# 03_-_CONNECTOR.net
KiCad netlist of a schematic drawn in Altium Designer
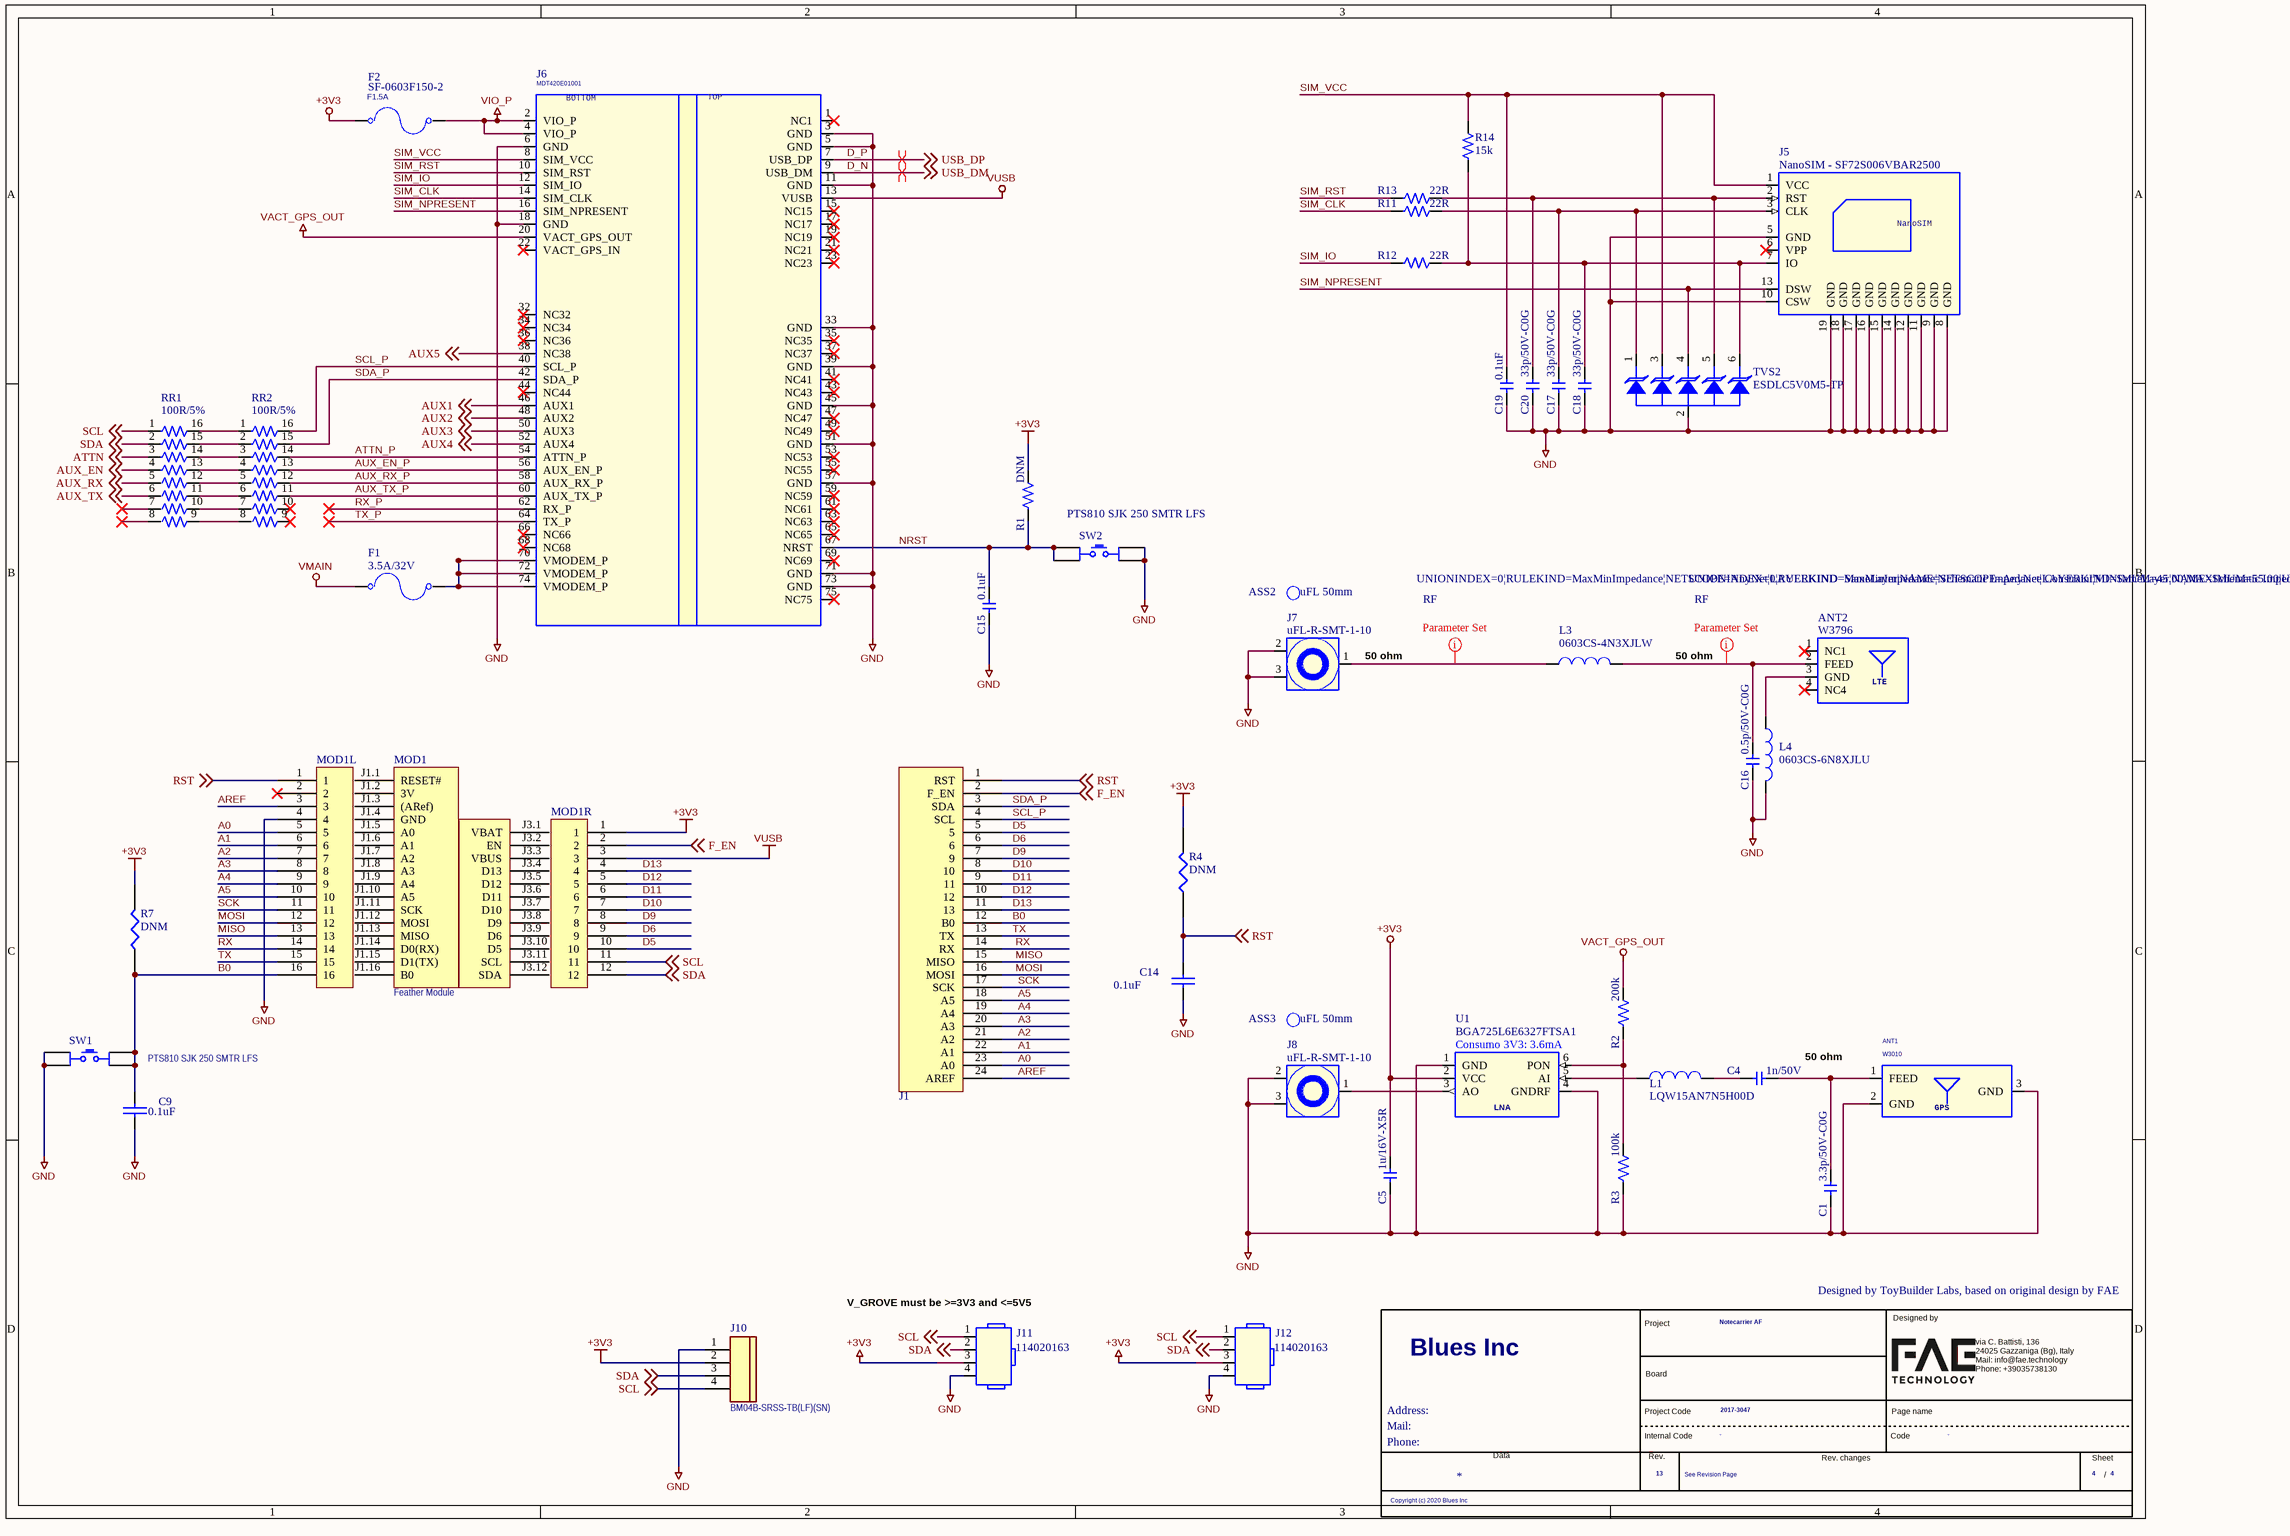
[diagram p0: 03 - CONNECTOR.SchDoc]

(export (version "E")
  (design (tool "Eeschema 10.0.6"))
  (components
    (comp (ref "*")
      (value "MyBlues")
      (fields
        (field (name "ADDRESS") "Address:")
        (field (name "COPYRIGHT") "Copyright (c) 2020 Blues Inc")
        (field (name "CUSTOMER CODE") "-")
        (field (name "CUSTOMERNAME") "Blues Inc")
        (field (name "DATABASE") "-")
        (field (name "DOCUMENTOREV") "See Revision Page")
        (field (name "MAIL") "Mail:")
        (field (name "NOME PROGETTO") "Notecarrier AF")
        (field (name "PAGE COUNT") "4")
        (field (name "PAGE NUMBER") "4")
        (field (name "PHONE") "Phone:")
        (field (name "PROJECT CODE") "2017-3047")
        (field (name "REVISION") "13")
      )
      (libsource (lib "*") (part "MyBlues"))
    )
    (comp (ref "ANT1")
      (value "W3010")
      (footprint "ANT-W3010")
      (description "ANTENNA CHIP 1.575GHZ D=3.2X10X2 W3010 PULSE SMT")
      (libsource (lib "*") (part "ANT - W3010 - GPS-GLONASS"))
    )
    (comp (ref "ANT2")
      (value "W3796")
      (footprint "ANT-W3796")
      (description "ANTENNA CHIP LTE D=40X7X3 W3796 PULSE SMT")
      (libsource (lib "*") (part "ANT - W3796 - LTE"))
    )
    (comp (ref "ASS2")
      (value "uFL 50mm")
      (description "CAVO COAX uFl-uFl 415-0086-050 HIROSE CINCH CONNECTIVITY SOLUTIONS JOHNSON")
      (libsource (lib "*") (part "0000_BASE SIMBOLO_OBJ"))
    )
    (comp (ref "ASS3")
      (value "uFL 50mm")
      (description "CAVO COAX uFl-uFl 415-0086-050 HIROSE CINCH CONNECTIVITY SOLUTIONS JOHNSON")
      (libsource (lib "*") (part "0000_BASE SIMBOLO_OBJ"))
    )
    (comp (ref "C1")
      (value "3.3p/50V-C0G")
      (footprint "CS-C-0402")
      (description "CHIP CAP.CER. 3.3pF 50V 5% C0G 0402")
      (libsource (lib "*") (part "CS-C-0402-3.3p/50V-C0G"))
    )
    (comp (ref "C4")
      (value "1n/50V")
      (footprint "CS-C-0402")
      (description "CHIP CAP.CER. 1nF 50V 10% X7R 0402")
      (libsource (lib "*") (part "CS-C-0402-1n/50V"))
    )
    (comp (ref "C5")
      (value "1u/16V-X5R")
      (footprint "CS-C-0402")
      (description "CHIP CAP.CER. 1uF 16V 10% X5R 0402")
      (libsource (lib "*") (part "CS-C-0402-1u/16-X5R"))
    )
    (comp (ref "C9")
      (value "0.1uF")
      (footprint "CS-C-0402")
      (description "CHIP CAP.CER. 100nF 16V 10% X7R 0402")
      (fields (field (name "MFR") "Yageo"))
      (libsource (lib "Cap_SCH") (part "CAP"))
    )
    (comp (ref "C14")
      (value "0.1uF")
      (footprint "CS-C-0402")
      (description "CHIP CAP.CER. 100nF 16V 10% X7R 0402")
      (fields (field (name "MFR") "Yageo"))
      (libsource (lib "Cap_SCH") (part "CAP"))
    )
    (comp (ref "C15")
      (value "0.1uF")
      (footprint "CS-C-0402")
      (description "CHIP CAP.CER. 100nF 16V 10% X7R 0402")
      (fields (field (name "MFR") "Yageo"))
      (libsource (lib "*") (part "CS-C-0402-100n/16V"))
    )
    (comp (ref "C16")
      (value "0.5p/50V-C0G")
      (footprint "CS-C-0402")
      (description "CHIP CAP.CER. 0.5pF 50V ±0.25 C0G 0402 GRM1555C1HR50CA01D MURATA")
      (libsource (lib "*") (part "CS-C-0402-0.5p/50V-C0G"))
    )
    (comp (ref "C17")
      (value "33p/50V-C0G")
      (footprint "CS-C-0402")
      (description "CHIP CAP.CER. 33pF 50V 5% C0G 0402")
      (libsource (lib "*") (part "CS-C-0402-33p/50V-C0G"))
    )
    (comp (ref "C18")
      (value "33p/50V-C0G")
      (footprint "CS-C-0402")
      (description "CHIP CAP.CER. 33pF 50V 5% C0G 0402")
      (libsource (lib "*") (part "CS-C-0402-33p/50V-C0G"))
    )
    (comp (ref "C19")
      (value "0.1uF")
      (footprint "CS-C-0402")
      (description "CHIP CAP.CER. 100nF 16V 10% X7R 0402")
      (fields (field (name "MFR") "Yageo"))
      (libsource (lib "*") (part "CS-C-0402-100n/16V"))
    )
    (comp (ref "C20")
      (value "33p/50V-C0G")
      (footprint "CS-C-0402")
      (description "CHIP CAP.CER. 33pF 50V 5% C0G 0402")
      (libsource (lib "*") (part "CS-C-0402-33p/50V-C0G"))
    )
    (comp (ref "F1")
      (value "3.5A/32V")
      (footprint "FS-0603")
      (description "FUSIBILE RAPIDO 3.5A 32V 0603 0603SFV350F/32-2 LITTELFUSE SMT")
      (fields (field (name "MPN") "0603SFV350F/32-2"))
      (libsource (lib "*") (part "RAPIDO - 0603SFV350F- 3.5A/32V"))
    )
    (comp (ref "F2")
      (value "SF-0603F150-2")
      (footprint "FS-0603")
      (description "FUSIBILE RAPIDO 1.5A 32V 0603 SF-0603F150-2 BOURNS SMT")
      (libsource (lib "*") (part "RAPIDO - SF-0603F150-2-1.5A/32V"))
    )
    (comp (ref "J1")
      (value "12X1")
      (footprint "WE24S - 2.54")
      (libsource (lib "ATA_BLS_002_NTCR_A0-01_SCHLIB") (part "SIDECON"))
    )
    (comp (ref "J5")
      (value "NanoSIM - SF72S006VBAR2500")
      (footprint "J-NANOSIM-SF72S006VBA")
      (description "CONN. NANOSIM 8P F/90° PUSH-PUSH SF72S006VBAR2500 JAE ELECTRONICS SMT")
      (libsource (lib "*") (part "NANOSIM - J-NANOSIM-SF72S006VBA"))
    )
    (comp (ref "J6")
      (value "MDT420E01001")
      (footprint "J-75-0050-MOS-M2-E")
      (description "CONN. M.2 75P M/90° P=0.5 MDT420E01001 AMPHENOL SMT")
      (libsource (lib "*") (part "AMPHENOL-75 - M-2 KEY E_13"))
    )
    (comp (ref "J7")
      (value "uFL-R-SMT-1-10")
      (footprint "J-3-MDS-UFL")
      (description "CONN. RF M U.FL-R-SMT-1(10) HIROSE SMT")
      (libsource (lib "*") (part "UFL - U-FL-R-SMT-1-10"))
    )
    (comp (ref "J8")
      (value "uFL-R-SMT-1-10")
      (footprint "J-3-MDS-UFL")
      (description "CONN. RF M U.FL-R-SMT-1(10) HIROSE SMT")
      (libsource (lib "*") (part "UFL - U-FL-R-SMT-1-10"))
    )
    (comp (ref "J10")
      (value "BM04B-SRSS-TB(LF)(SN)")
      (footprint "JST_BM04B-SRSS-TB")
      (description "Wire-to-board, 1mm, SMT Vert, 4POS")
      (fields (field (name "MANUFACTURER") "JST"))
      (libsource (lib "TBL Connectors") (part "JST_BM04B-SRSS-TB"))
    )
    (comp (ref "J11")
      (value "114020163")
      (footprint "J-4-0200-MDS-GROVE")
      (description "CONN. GROVE 4P M/D P=2 114020163 SEEDSTUDIO SMT")
      (libsource (lib "*") (part "GROVE - J-4-0200-MDS-GROVE"))
    )
    (comp (ref "J12")
      (value "114020163")
      (footprint "J-4-0200-MDS-GROVE")
      (description "CONN. GROVE 4P M/D P=2 114020163 SEEDSTUDIO SMT")
      (libsource (lib "*") (part "GROVE - J-4-0200-MDS-GROVE"))
    )
    (comp (ref "L1")
      (value "LQW15AN7N5H00D")
      (footprint "LS-0402")
      (description "INDUTTANZA 7.5nH 0.57A 3% A FILO 0402 LQW15AN7N5H00D MURATA SMT")
      (libsource (lib "*") (part "L - LQW15AN7N5H00D - 7.5n/0.57A"))
    )
    (comp (ref "L3")
      (value "0603CS-4N3XJLW")
      (footprint "LS-0603CS")
      (description "INDUTTANZA 4.3nH 0.7A 5% 0603 0603CS-4N3XJLW COILCRAFT SMT")
      (libsource (lib "*") (part "L - 0603CS-4N3XJLW-4.3n/0.7A"))
    )
    (comp (ref "L4")
      (value "0603CS-6N8XJLU")
      (footprint "LS-0603CS")
      (description "INDUTTANZA 6.8nH 0.7A 5% 0603 0603CS-6N8XJLU COILCRAFT SMT")
      (libsource (lib "*") (part "L - 0603CS-6N8XJLU-6.8n/0.7A"))
    )
    (comp (ref "MOD1")
      (value "Feather Module")
      (footprint "FEATHER_COMMON_MOUNTING")
      (description "Socket Footprint for Typical Adafruit Feather Module, SMT socket type")
      (libsource (lib "Notebox Integrated Library") (part "FEATHER_COMMON_MOUNTING"))
    )
    (comp (ref "MOD1L")
      (value "Socket 16-Pin, 0.100 inch (0.335 inch body)")
      (footprint "SOCKET_LFB_16")
      (description "Socket 16-Pin, 0.100 in")
      (libsource (lib "TBLI-Headers") (part "SOCKET_LFB_16"))
    )
    (comp (ref "MOD1R")
      (value "Socket 12-Pin, 0.100 inch (0.335 inch body)")
      (footprint "SOCKET_LFB_12")
      (description "Socket 12-Pin, 0.100 in")
      (libsource (lib "TBLI-Headers") (part "SOCKET_LFB_12"))
    )
    (comp (ref "R1")
      (value "DNM")
      (footprint "RS-0402")
      (description "CHIP RES. 1K 0402 1/16W 1%")
      (libsource (lib "*") (part "RS-0402-1k"))
    )
    (comp (ref "R2")
      (value "200k")
      (footprint "RS-0402")
      (description "CHIP RES. 200K 0402 1/16W 1%")
      (libsource (lib "*") (part "RS-0402-200k"))
    )
    (comp (ref "R3")
      (value "100k")
      (footprint "RS-0402")
      (description "CHIP RES. 100K 0402 1/16W 1%")
      (libsource (lib "*") (part "RS-0402-100k"))
    )
    (comp (ref "R4")
      (value "DNM")
      (footprint "RS-0402")
      (description "SMD Resistors")
      (libsource (lib "Res_SCH") (part "R1_S"))
    )
    (comp (ref "R7")
      (value "DNM")
      (footprint "RS-0402")
      (description "SMD Resistors")
      (libsource (lib "Res_SCH") (part "R1_S"))
    )
    (comp (ref "R11")
      (value "22R")
      (footprint "RS-0603")
      (description "CHIP RES. 22R 0603 1/16W 1%")
      (libsource (lib "*") (part "RS-0603-22r"))
    )
    (comp (ref "R12")
      (value "22R")
      (footprint "RS-0603")
      (description "CHIP RES. 22R 0603 1/16W 1%")
      (libsource (lib "*") (part "RS-0603-22r"))
    )
    (comp (ref "R13")
      (value "22R")
      (footprint "RS-0603")
      (description "CHIP RES. 22R 0603 1/16W 1%")
      (libsource (lib "*") (part "RS-0603-22r"))
    )
    (comp (ref "R14")
      (value "15k")
      (footprint "RS-0402")
      (description "CHIP RES. 15K 0402 1/16W 1%")
      (libsource (lib "*") (part "RS-0402-15k"))
    )
    (comp (ref "RR1")
      (value "100R/5%")
      (footprint "RR-8X-1506")
      (description "RETE RESISTIVA 8R sing. 100R 5% 1506 CONVEX CAY16-101J8LF BOURNS SMT")
      (libsource (lib "*") (part "RR-8X-1506-100r/5%"))
    )
    (comp (ref "RR2")
      (value "100R/5%")
      (footprint "RR-8X-1506")
      (description "RETE RESISTIVA 8R sing. 100R 5% 1506 CONVEX CAY16-101J8LF BOURNS SMT")
      (libsource (lib "*") (part "RR-8X-1506-100r/5%"))
    )
    (comp (ref "SW1")
      (value "PTS810 SJK 250 SMTR LFS")
      (footprint "CK-PTS810-SJx")
      (description "SWITCH TACTILE SPST-NO 0.05A 12V 4.2 mm x 3.2 mm")
      (fields (field (name "MANUFACTURER") "C&K"))
      (libsource (lib "TBL Switches and Buttons") (part "CK_PTS810 SJK 250 SMTR LFS"))
    )
    (comp (ref "SW2")
      (value "PTS810 SJK 250 SMTR LFS")
      (footprint "CK-PTS810-SJx")
      (description "SWITCH TACTILE SPST-NO 0.05A 12V 4.2 mm x 3.2 mm")
      (fields (field (name "MANUFACTURER") "C&K"))
      (libsource (lib "TBL Switches and Buttons") (part "CK_PTS810 SJK 250 SMTR LFS"))
    )
    (comp (ref "TVS2")
      (value "ESDLC5V0M5-TP")
      (footprint "SOT666")
      (description "DIODO TVS TRANSIL UNIDIR. 20W 5V ESDLC5V0M5-TP SOT563 SMT")
      (libsource (lib "*") (part "TVS-UNI5x - ESDLC5V0M5-TP - 5V"))
    )
    (comp (ref "U1")
      (value "BGA725L6E6327FTSA1")
      (footprint "XFDFN6")
      (description "INTEGRATO BGA725L6E6327FTSA1 INFINEON TSLP-6 SMT")
      (fields (field (name "CONSUMO") "Consumo 3V3: 3.6mA"))
      (libsource (lib "*") (part "LNA-RF - BGA725L6E6327FTSA1"))
    )
  )
  (nets
    (net (code "1") (name "+3V3") (class "Default")
      (node (ref "C5") (pin "1") (pinfunction "1_1") (pintype "passive"))
      (node (ref "F2") (pin "1") (pinfunction "1_1") (pintype "passive"))
      (node (ref "J10") (pin "2") (pinfunction "2_2") (pintype "passive"))
      (node (ref "J11") (pin "3") (pinfunction "3_3") (pintype "passive"))
      (node (ref "J12") (pin "3") (pinfunction "3_3") (pintype "passive"))
      (node (ref "MOD1R") (pin "1") (pinfunction "1_1") (pintype "passive"))
      (node (ref "R1") (pin "2") (pinfunction "2_2") (pintype "passive"))
      (node (ref "R4") (pin "2") (pinfunction "2_2") (pintype "passive"))
      (node (ref "R7") (pin "2") (pinfunction "2_2") (pintype "passive"))
      (node (ref "U1") (pin "2") (pinfunction "VCC_2") (pintype "power_in"))
    )
    (net (code "2") (name "/A0") (class "Default")
      (node (ref "J1") (pin "23") (pinfunction "A0_23") (pintype "passive"))
      (node (ref "MOD1L") (pin "5") (pinfunction "5_5") (pintype "passive"))
    )
    (net (code "3") (name "/A1") (class "Default")
      (node (ref "J1") (pin "22") (pinfunction "A1_22") (pintype "passive"))
      (node (ref "MOD1L") (pin "6") (pinfunction "6_6") (pintype "passive"))
    )
    (net (code "4") (name "/A2") (class "Default")
      (node (ref "J1") (pin "21") (pinfunction "A2_21") (pintype "passive"))
      (node (ref "MOD1L") (pin "7") (pinfunction "7_7") (pintype "passive"))
    )
    (net (code "5") (name "/A3") (class "Default")
      (node (ref "J1") (pin "20") (pinfunction "A3_20") (pintype "passive"))
      (node (ref "MOD1L") (pin "8") (pinfunction "8_8") (pintype "passive"))
    )
    (net (code "6") (name "/A4") (class "Default")
      (node (ref "J1") (pin "19") (pinfunction "A4_19") (pintype "passive"))
      (node (ref "MOD1L") (pin "9") (pinfunction "9_9") (pintype "passive"))
    )
    (net (code "7") (name "/A5") (class "Default")
      (node (ref "J1") (pin "18") (pinfunction "A5_18") (pintype "passive"))
      (node (ref "MOD1L") (pin "10") (pinfunction "10_10") (pintype "passive"))
    )
    (net (code "8") (name "/AREF") (class "Default")
      (node (ref "J1") (pin "24") (pinfunction "AREF_24") (pintype "passive"))
      (node (ref "MOD1L") (pin "3") (pinfunction "3_3") (pintype "passive"))
    )
    (net (code "9") (name "/ATTN_P") (class "Default")
      (node (ref "J6") (pin "54") (pinfunction "ATTN_P_54") (pintype "passive"))
      (node (ref "RR2") (pin "14") (pinfunction "14_14") (pintype "passive"))
    )
    (net (code "10") (name "/AUX_EN_P") (class "Default")
      (node (ref "J6") (pin "56") (pinfunction "AUX_EN_P_56") (pintype "passive"))
      (node (ref "RR2") (pin "13") (pinfunction "13_13") (pintype "passive"))
    )
    (net (code "11") (name "/AUX_RX_P") (class "Default")
      (node (ref "J6") (pin "58") (pinfunction "AUX_RX_P_58") (pintype "passive"))
      (node (ref "RR2") (pin "12") (pinfunction "12_12") (pintype "passive"))
    )
    (net (code "12") (name "/AUX_TX_P") (class "Default")
      (node (ref "J6") (pin "60") (pinfunction "AUX_TX_P_60") (pintype "passive"))
      (node (ref "RR2") (pin "11") (pinfunction "11_11") (pintype "passive"))
    )
    (net (code "13") (name "/B0") (class "Default")
      (node (ref "C9") (pin "1") (pinfunction "1_1") (pintype "passive"))
      (node (ref "J1") (pin "12") (pinfunction "B0_12") (pintype "passive"))
      (node (ref "MOD1L") (pin "16") (pinfunction "16_16") (pintype "passive"))
      (node (ref "R7") (pin "1") (pinfunction "1_1") (pintype "passive"))
      (node (ref "SW1") (pin "1") (pinfunction "1_1") (pintype "passive"))
      (node (ref "SW1") (pin "2") (pinfunction "2_2") (pintype "passive"))
    )
    (net (code "14") (name "/D5") (class "Default")
      (node (ref "J1") (pin "5") (pinfunction "5_5") (pintype "passive"))
      (node (ref "MOD1R") (pin "10") (pinfunction "10_10") (pintype "passive"))
    )
    (net (code "15") (name "/D6") (class "Default")
      (node (ref "J1") (pin "6") (pinfunction "6_6") (pintype "passive"))
      (node (ref "MOD1R") (pin "9") (pinfunction "9_9") (pintype "passive"))
    )
    (net (code "16") (name "/D9") (class "Default")
      (node (ref "J1") (pin "7") (pinfunction "9_7") (pintype "passive"))
      (node (ref "MOD1R") (pin "8") (pinfunction "8_8") (pintype "passive"))
    )
    (net (code "17") (name "/D10") (class "Default")
      (node (ref "J1") (pin "8") (pinfunction "10_8") (pintype "passive"))
      (node (ref "MOD1R") (pin "7") (pinfunction "7_7") (pintype "passive"))
    )
    (net (code "18") (name "/D11") (class "Default")
      (node (ref "J1") (pin "9") (pinfunction "11_9") (pintype "passive"))
      (node (ref "MOD1R") (pin "6") (pinfunction "6_6") (pintype "passive"))
    )
    (net (code "19") (name "/D12") (class "Default")
      (node (ref "J1") (pin "10") (pinfunction "12_10") (pintype "passive"))
      (node (ref "MOD1R") (pin "5") (pinfunction "5_5") (pintype "passive"))
    )
    (net (code "20") (name "/D13") (class "Default")
      (node (ref "J1") (pin "11") (pinfunction "13_11") (pintype "passive"))
      (node (ref "MOD1R") (pin "4") (pinfunction "4_4") (pintype "passive"))
    )
    (net (code "21") (name "/MISO") (class "Default")
      (node (ref "J1") (pin "15") (pinfunction "MISO_15") (pintype "passive"))
      (node (ref "MOD1L") (pin "13") (pinfunction "13_13") (pintype "passive"))
    )
    (net (code "22") (name "/MOSI") (class "Default")
      (node (ref "J1") (pin "16") (pinfunction "MOSI_16") (pintype "passive"))
      (node (ref "MOD1L") (pin "12") (pinfunction "12_12") (pintype "passive"))
    )
    (net (code "23") (name "/NRST") (class "Default")
      (node (ref "C15") (pin "1") (pinfunction "1_1") (pintype "passive"))
      (node (ref "J6") (pin "67") (pinfunction "NRST_67") (pintype "passive"))
      (node (ref "R1") (pin "1") (pinfunction "1_1") (pintype "passive"))
      (node (ref "SW2") (pin "3") (pinfunction "3_3") (pintype "passive"))
      (node (ref "SW2") (pin "4") (pinfunction "4_4") (pintype "passive"))
    )
    (net (code "24") (name "/RX") (class "Default")
      (node (ref "J1") (pin "14") (pinfunction "RX_14") (pintype "passive"))
      (node (ref "MOD1L") (pin "14") (pinfunction "14_14") (pintype "passive"))
    )
    (net (code "25") (name "/RX_P") (class "Default")
      (node (ref "J6") (pin "62") (pinfunction "RX_P_62") (pintype "passive+no_connect"))
    )
    (net (code "26") (name "/SCK") (class "Default")
      (node (ref "J1") (pin "17") (pinfunction "SCK_17") (pintype "passive"))
      (node (ref "MOD1L") (pin "11") (pinfunction "11_11") (pintype "passive"))
    )
    (net (code "27") (name "/SCL_P") (class "Default")
      (node (ref "J1") (pin "4") (pinfunction "SCL_4") (pintype "passive"))
      (node (ref "J6") (pin "40") (pinfunction "SCL_P_40") (pintype "passive"))
      (node (ref "RR2") (pin "16") (pinfunction "16_16") (pintype "passive"))
    )
    (net (code "28") (name "/SDA_P") (class "Default")
      (node (ref "J1") (pin "3") (pinfunction "SDA_3") (pintype "passive"))
      (node (ref "J6") (pin "42") (pinfunction "SDA_P_42") (pintype "passive"))
      (node (ref "RR2") (pin "15") (pinfunction "15_15") (pintype "passive"))
    )
    (net (code "29") (name "/SIM_CLK") (class "Default")
      (node (ref "J6") (pin "14") (pinfunction "SIM_CLK_14") (pintype "passive"))
      (node (ref "R11") (pin "1") (pinfunction "1_1") (pintype "passive"))
    )
    (net (code "30") (name "/SIM_IO") (class "Default")
      (node (ref "J6") (pin "12") (pinfunction "SIM_IO_12") (pintype "passive"))
      (node (ref "R12") (pin "1") (pinfunction "1_1") (pintype "passive"))
    )
    (net (code "31") (name "/SIM_NPRESENT") (class "Default")
      (node (ref "J5") (pin "13") (pinfunction "DSW_13") (pintype "passive"))
      (node (ref "J6") (pin "16") (pinfunction "SIM_NPRESENT_16") (pintype "passive"))
      (node (ref "TVS2") (pin "4") (pinfunction "C4_4") (pintype "passive"))
    )
    (net (code "32") (name "/SIM_RST") (class "Default")
      (node (ref "J6") (pin "10") (pinfunction "SIM_RST_10") (pintype "passive"))
      (node (ref "R13") (pin "1") (pinfunction "1_1") (pintype "passive"))
    )
    (net (code "33") (name "/SIM_VCC") (class "Default")
      (node (ref "C19") (pin "1") (pinfunction "1_1") (pintype "passive"))
      (node (ref "J5") (pin "1") (pinfunction "VCC_1") (pintype "power_in"))
      (node (ref "J6") (pin "8") (pinfunction "SIM_VCC_8") (pintype "passive"))
      (node (ref "R14") (pin "2") (pinfunction "2_2") (pintype "passive"))
      (node (ref "TVS2") (pin "3") (pinfunction "C3_3") (pintype "passive"))
    )
    (net (code "34") (name "/TX") (class "Default")
      (node (ref "J1") (pin "13") (pinfunction "TX_13") (pintype "passive"))
      (node (ref "MOD1L") (pin "15") (pinfunction "15_15") (pintype "passive"))
    )
    (net (code "35") (name "/TX_P") (class "Default")
      (node (ref "J6") (pin "64") (pinfunction "TX_P_64") (pintype "passive+no_connect"))
    )
    (net (code "36") (name "ATTN") (class "Default")
      (node (ref "RR1") (pin "3") (pinfunction "3_3") (pintype "passive"))
    )
    (net (code "37") (name "AUX1") (class "Default")
      (node (ref "J6") (pin "46") (pinfunction "AUX1_46") (pintype "passive"))
    )
    (net (code "38") (name "AUX2") (class "Default")
      (node (ref "J6") (pin "48") (pinfunction "AUX2_48") (pintype "passive"))
    )
    (net (code "39") (name "AUX3") (class "Default")
      (node (ref "J6") (pin "50") (pinfunction "AUX3_50") (pintype "passive"))
    )
    (net (code "40") (name "AUX4") (class "Default")
      (node (ref "J6") (pin "52") (pinfunction "AUX4_52") (pintype "passive"))
    )
    (net (code "41") (name "AUX5") (class "Default")
      (node (ref "J6") (pin "38") (pinfunction "NC38_38") (pintype "passive"))
    )
    (net (code "42") (name "AUX_EN") (class "Default")
      (node (ref "RR1") (pin "4") (pinfunction "4_4") (pintype "passive"))
    )
    (net (code "43") (name "AUX_RX") (class "Default")
      (node (ref "RR1") (pin "5") (pinfunction "5_5") (pintype "passive"))
    )
    (net (code "44") (name "AUX_TX") (class "Default")
      (node (ref "RR1") (pin "6") (pinfunction "6_6") (pintype "passive"))
    )
    (net (code "45") (name "F_EN") (class "Default")
      (node (ref "J1") (pin "2") (pinfunction "F_EN_2") (pintype "passive"))
      (node (ref "MOD1R") (pin "2") (pinfunction "2_2") (pintype "passive"))
    )
    (net (code "46") (name "GND") (class "Default")
      (node (ref "ANT1") (pin "2") (pinfunction "GND_2") (pintype "power_in"))
      (node (ref "ANT1") (pin "3") (pinfunction "GND_3") (pintype "power_in"))
      (node (ref "C1") (pin "2") (pinfunction "2_2") (pintype "passive"))
      (node (ref "C14") (pin "2") (pinfunction "2_2") (pintype "passive"))
      (node (ref "C15") (pin "2") (pinfunction "2_2") (pintype "passive"))
      (node (ref "C16") (pin "2") (pinfunction "2_2") (pintype "passive"))
      (node (ref "C17") (pin "2") (pinfunction "2_2") (pintype "passive"))
      (node (ref "C18") (pin "2") (pinfunction "2_2") (pintype "passive"))
      (node (ref "C19") (pin "2") (pinfunction "2_2") (pintype "passive"))
      (node (ref "C20") (pin "2") (pinfunction "2_2") (pintype "passive"))
      (node (ref "C5") (pin "2") (pinfunction "2_2") (pintype "passive"))
      (node (ref "C9") (pin "2") (pinfunction "2_2") (pintype "passive"))
      (node (ref "J10") (pin "1") (pinfunction "1_1") (pintype "passive"))
      (node (ref "J11") (pin "4") (pinfunction "4_4") (pintype "passive"))
      (node (ref "J12") (pin "4") (pinfunction "4_4") (pintype "passive"))
      (node (ref "J5") (pin "10") (pinfunction "CSW_10") (pintype "passive"))
      (node (ref "J5") (pin "11") (pinfunction "GND_11") (pintype "power_in"))
      (node (ref "J5") (pin "12") (pinfunction "GND_12") (pintype "power_in"))
      (node (ref "J5") (pin "14") (pinfunction "GND_14") (pintype "power_in"))
      (node (ref "J5") (pin "15") (pinfunction "GND_15") (pintype "power_in"))
      (node (ref "J5") (pin "16") (pinfunction "GND_16") (pintype "power_in"))
      (node (ref "J5") (pin "17") (pinfunction "GND_17") (pintype "power_in"))
      (node (ref "J5") (pin "18") (pinfunction "GND_18") (pintype "power_in"))
      (node (ref "J5") (pin "19") (pinfunction "GND_19") (pintype "power_in"))
      (node (ref "J5") (pin "5") (pinfunction "GND_5") (pintype "power_in"))
      (node (ref "J5") (pin "8") (pinfunction "GND_8") (pintype "power_in"))
      (node (ref "J5") (pin "9") (pinfunction "GND_9") (pintype "power_in"))
      (node (ref "J6") (pin "11") (pinfunction "GND_11") (pintype "power_in"))
      (node (ref "J6") (pin "18") (pinfunction "GND_18") (pintype "power_in"))
      (node (ref "J6") (pin "3") (pinfunction "GND_3") (pintype "power_in"))
      (node (ref "J6") (pin "33") (pinfunction "GND_33") (pintype "power_in"))
      (node (ref "J6") (pin "39") (pinfunction "GND_39") (pintype "power_in"))
      (node (ref "J6") (pin "45") (pinfunction "GND_45") (pintype "power_in"))
      (node (ref "J6") (pin "5") (pinfunction "GND_5") (pintype "power_in"))
      (node (ref "J6") (pin "51") (pinfunction "GND_51") (pintype "power_in"))
      (node (ref "J6") (pin "57") (pinfunction "GND_57") (pintype "power_in"))
      (node (ref "J6") (pin "6") (pinfunction "GND_6") (pintype "power_in"))
      (node (ref "J6") (pin "71") (pinfunction "GND_71") (pintype "power_in"))
      (node (ref "J6") (pin "73") (pinfunction "GND_73") (pintype "power_in"))
      (node (ref "J7") (pin "2") (pinfunction "2_2") (pintype "passive"))
      (node (ref "J7") (pin "3") (pinfunction "3_3") (pintype "passive"))
      (node (ref "J8") (pin "2") (pinfunction "2_2") (pintype "passive"))
      (node (ref "J8") (pin "3") (pinfunction "3_3") (pintype "passive"))
      (node (ref "L4") (pin "2") (pinfunction "A_2") (pintype "passive"))
      (node (ref "MOD1L") (pin "4") (pinfunction "4_4") (pintype "passive"))
      (node (ref "R3") (pin "1") (pinfunction "1_1") (pintype "passive"))
      (node (ref "SW1") (pin "3") (pinfunction "3_3") (pintype "passive"))
      (node (ref "SW1") (pin "4") (pinfunction "4_4") (pintype "passive"))
      (node (ref "SW2") (pin "1") (pinfunction "1_1") (pintype "passive"))
      (node (ref "SW2") (pin "2") (pinfunction "2_2") (pintype "passive"))
      (node (ref "TVS2") (pin "2") (pinfunction "A2_2") (pintype "passive"))
      (node (ref "U1") (pin "1") (pinfunction "GND_1") (pintype "power_in"))
      (node (ref "U1") (pin "4") (pinfunction "GNDRF_4") (pintype "power_in"))
    )
    (net (code "47") (name "Net-(ANT1-FEED)") (class "Default")
      (node (ref "ANT1") (pin "1") (pinfunction "FEED_1") (pintype "passive"))
      (node (ref "C1") (pin "1") (pinfunction "1_1") (pintype "passive"))
      (node (ref "C4") (pin "2") (pinfunction "2_2") (pintype "passive"))
    )
    (net (code "48") (name "Net-(ANT2-FEED)") (class "Default")
      (node (ref "ANT2") (pin "2") (pinfunction "FEED_2") (pintype "passive"))
      (node (ref "C16") (pin "1") (pinfunction "1_1") (pintype "passive"))
      (node (ref "L3") (pin "2") (pinfunction "A_2") (pintype "passive"))
    )
    (net (code "49") (name "Net-(ANT2-GND)") (class "Default")
      (node (ref "ANT2") (pin "3") (pinfunction "GND_3") (pintype "power_in"))
      (node (ref "L4") (pin "1") (pinfunction "C_1") (pintype "passive"))
    )
    (net (code "50") (name "Net-(F1-Pad2)") (class "Default")
      (node (ref "F1") (pin "2") (pinfunction "2_2") (pintype "passive"))
      (node (ref "J6") (pin "70") (pinfunction "VMODEM_P_70") (pintype "power_in"))
      (node (ref "J6") (pin "72") (pinfunction "VMODEM_P_72") (pintype "power_in"))
      (node (ref "J6") (pin "74") (pinfunction "VMODEM_P_74") (pintype "power_in"))
    )
    (net (code "51") (name "Net-(J5-CLK)") (class "Default")
      (node (ref "C17") (pin "1") (pinfunction "1_1") (pintype "passive"))
      (node (ref "J5") (pin "3") (pinfunction "CLK_3") (pintype "input"))
      (node (ref "R11") (pin "2") (pinfunction "2_2") (pintype "passive"))
      (node (ref "TVS2") (pin "1") (pinfunction "C1_1") (pintype "passive"))
    )
    (net (code "52") (name "Net-(J5-IO)") (class "Default")
      (node (ref "C18") (pin "1") (pinfunction "1_1") (pintype "passive"))
      (node (ref "J5") (pin "7") (pinfunction "IO_7") (pintype "bidirectional"))
      (node (ref "R12") (pin "2") (pinfunction "2_2") (pintype "passive"))
      (node (ref "R14") (pin "1") (pinfunction "1_1") (pintype "passive"))
      (node (ref "TVS2") (pin "6") (pinfunction "C6_6") (pintype "passive"))
    )
    (net (code "53") (name "Net-(J5-RST)") (class "Default")
      (node (ref "C20") (pin "1") (pinfunction "1_1") (pintype "passive"))
      (node (ref "J5") (pin "2") (pinfunction "RST_2") (pintype "input"))
      (node (ref "R13") (pin "2") (pinfunction "2_2") (pintype "passive"))
      (node (ref "TVS2") (pin "5") (pinfunction "A5_5") (pintype "passive"))
    )
    (net (code "54") (name "Net-(L1-A)") (class "Default")
      (node (ref "C4") (pin "1") (pinfunction "1_1") (pintype "passive"))
      (node (ref "L1") (pin "2") (pinfunction "A_2") (pintype "passive"))
    )
    (net (code "55") (name "Net-(L1-C)") (class "Default")
      (node (ref "L1") (pin "1") (pinfunction "C_1") (pintype "passive"))
      (node (ref "U1") (pin "5") (pinfunction "AI_5") (pintype "input"))
    )
    (net (code "56") (name "Net-(L3-C)") (class "Default")
      (node (ref "J7") (pin "1") (pinfunction "1_1") (pintype "passive"))
      (node (ref "L3") (pin "1") (pinfunction "C_1") (pintype "passive"))
    )
    (net (code "57") (name "Net-(RR1-Pad9)") (class "Default")
      (node (ref "RR1") (pin "9") (pinfunction "9_9") (pintype "passive"))
      (node (ref "RR2") (pin "8") (pinfunction "8_8") (pintype "passive"))
    )
    (net (code "58") (name "Net-(RR1-Pad10)") (class "Default")
      (node (ref "RR1") (pin "10") (pinfunction "10_10") (pintype "passive"))
      (node (ref "RR2") (pin "7") (pinfunction "7_7") (pintype "passive"))
    )
    (net (code "59") (name "Net-(RR1-Pad11)") (class "Default")
      (node (ref "RR1") (pin "11") (pinfunction "11_11") (pintype "passive"))
      (node (ref "RR2") (pin "6") (pinfunction "6_6") (pintype "passive"))
    )
    (net (code "60") (name "Net-(RR1-Pad12)") (class "Default")
      (node (ref "RR1") (pin "12") (pinfunction "12_12") (pintype "passive"))
      (node (ref "RR2") (pin "5") (pinfunction "5_5") (pintype "passive"))
    )
    (net (code "61") (name "Net-(RR1-Pad13)") (class "Default")
      (node (ref "RR1") (pin "13") (pinfunction "13_13") (pintype "passive"))
      (node (ref "RR2") (pin "4") (pinfunction "4_4") (pintype "passive"))
    )
    (net (code "62") (name "Net-(RR1-Pad14)") (class "Default")
      (node (ref "RR1") (pin "14") (pinfunction "14_14") (pintype "passive"))
      (node (ref "RR2") (pin "3") (pinfunction "3_3") (pintype "passive"))
    )
    (net (code "63") (name "Net-(RR1-Pad15)") (class "Default")
      (node (ref "RR1") (pin "15") (pinfunction "15_15") (pintype "passive"))
      (node (ref "RR2") (pin "2") (pinfunction "2_2") (pintype "passive"))
    )
    (net (code "64") (name "Net-(RR1-Pad16)") (class "Default")
      (node (ref "RR1") (pin "16") (pinfunction "16_16") (pintype "passive"))
      (node (ref "RR2") (pin "1") (pinfunction "1_1") (pintype "passive"))
    )
    (net (code "65") (name "Net-(U1-AO)") (class "Default")
      (node (ref "J8") (pin "1") (pinfunction "1_1") (pintype "passive"))
      (node (ref "U1") (pin "3") (pinfunction "AO_3") (pintype "output"))
    )
    (net (code "66") (name "Net-(U1-PON)") (class "Default")
      (node (ref "R2") (pin "1") (pinfunction "1_1") (pintype "passive"))
      (node (ref "R3") (pin "2") (pinfunction "2_2") (pintype "passive"))
      (node (ref "U1") (pin "6") (pinfunction "PON_6") (pintype "input"))
    )
    (net (code "67") (name "RST") (class "Default")
      (node (ref "C14") (pin "1") (pinfunction "1_1") (pintype "passive"))
      (node (ref "J1") (pin "1") (pinfunction "RST_1") (pintype "passive"))
      (node (ref "MOD1L") (pin "1") (pinfunction "1_1") (pintype "passive"))
      (node (ref "R4") (pin "1") (pinfunction "1_1") (pintype "passive"))
    )
    (net (code "68") (name "SCL") (class "Default")
      (node (ref "J10") (pin "4") (pinfunction "4_4") (pintype "passive"))
      (node (ref "J11") (pin "1") (pinfunction "1_1") (pintype "passive"))
      (node (ref "J12") (pin "1") (pinfunction "1_1") (pintype "passive"))
      (node (ref "MOD1R") (pin "11") (pinfunction "11_11") (pintype "passive"))
      (node (ref "RR1") (pin "1") (pinfunction "1_1") (pintype "passive"))
    )
    (net (code "69") (name "SDA") (class "Default")
      (node (ref "J10") (pin "3") (pinfunction "3_3") (pintype "passive"))
      (node (ref "J11") (pin "2") (pinfunction "2_2") (pintype "passive"))
      (node (ref "J12") (pin "2") (pinfunction "2_2") (pintype "passive"))
      (node (ref "MOD1R") (pin "12") (pinfunction "12_12") (pintype "passive"))
      (node (ref "RR1") (pin "2") (pinfunction "2_2") (pintype "passive"))
    )
    (net (code "70") (name "USB_DM") (class "Default")
      (node (ref "J6") (pin "9") (pinfunction "USB_DM_9") (pintype "passive"))
    )
    (net (code "71") (name "USB_DP") (class "Default")
      (node (ref "J6") (pin "7") (pinfunction "USB_DP_7") (pintype "passive"))
    )
    (net (code "72") (name "VACT_GPS_OUT") (class "Default")
      (node (ref "J6") (pin "20") (pinfunction "VACT_GPS_OUT_20") (pintype "power_in"))
      (node (ref "R2") (pin "2") (pinfunction "2_2") (pintype "passive"))
    )
    (net (code "73") (name "VIO_P") (class "Default")
      (node (ref "F2") (pin "2") (pinfunction "2_2") (pintype "passive"))
      (node (ref "J6") (pin "2") (pinfunction "VIO_P_2") (pintype "power_in"))
      (node (ref "J6") (pin "4") (pinfunction "VIO_P_4") (pintype "power_in"))
    )
    (net (code "74") (name "VMAIN") (class "Default")
      (node (ref "F1") (pin "1") (pinfunction "1_1") (pintype "passive"))
    )
    (net (code "75") (name "VUSB") (class "Default")
      (node (ref "J6") (pin "13") (pinfunction "VUSB_13") (pintype "power_in"))
      (node (ref "MOD1R") (pin "3") (pinfunction "3_3") (pintype "passive"))
    )
    (net (code "76") (name "unconnected-(ANT2-NC1-Pad1)") (class "Default")
      (node (ref "ANT2") (pin "1") (pinfunction "NC1_1") (pintype "passive+no_connect"))
    )
    (net (code "77") (name "unconnected-(ANT2-NC4-Pad4)") (class "Default")
      (node (ref "ANT2") (pin "4") (pinfunction "NC4_4") (pintype "passive+no_connect"))
    )
    (net (code "78") (name "unconnected-(J5-VPP-Pad6)") (class "Default")
      (node (ref "J5") (pin "6") (pinfunction "VPP_6") (pintype "passive+no_connect"))
    )
    (net (code "79") (name "unconnected-(J6-NC1-Pad1)") (class "Default")
      (node (ref "J6") (pin "1") (pinfunction "NC1_1") (pintype "passive+no_connect"))
    )
    (net (code "80") (name "unconnected-(J6-NC15-Pad15)") (class "Default")
      (node (ref "J6") (pin "15") (pinfunction "NC15_15") (pintype "passive+no_connect"))
    )
    (net (code "81") (name "unconnected-(J6-NC17-Pad17)") (class "Default")
      (node (ref "J6") (pin "17") (pinfunction "NC17_17") (pintype "passive+no_connect"))
    )
    (net (code "82") (name "unconnected-(J6-NC19-Pad19)") (class "Default")
      (node (ref "J6") (pin "19") (pinfunction "NC19_19") (pintype "passive+no_connect"))
    )
    (net (code "83") (name "unconnected-(J6-NC21-Pad21)") (class "Default")
      (node (ref "J6") (pin "21") (pinfunction "NC21_21") (pintype "passive+no_connect"))
    )
    (net (code "84") (name "unconnected-(J6-NC23-Pad23)") (class "Default")
      (node (ref "J6") (pin "23") (pinfunction "NC23_23") (pintype "passive+no_connect"))
    )
    (net (code "85") (name "unconnected-(J6-NC32-Pad32)") (class "Default")
      (node (ref "J6") (pin "32") (pinfunction "NC32_32") (pintype "passive+no_connect"))
    )
    (net (code "86") (name "unconnected-(J6-NC34-Pad34)") (class "Default")
      (node (ref "J6") (pin "34") (pinfunction "NC34_34") (pintype "passive+no_connect"))
    )
    (net (code "87") (name "unconnected-(J6-NC35-Pad35)") (class "Default")
      (node (ref "J6") (pin "35") (pinfunction "NC35_35") (pintype "passive+no_connect"))
    )
    (net (code "88") (name "unconnected-(J6-NC36-Pad36)") (class "Default")
      (node (ref "J6") (pin "36") (pinfunction "NC36_36") (pintype "passive+no_connect"))
    )
    (net (code "89") (name "unconnected-(J6-NC37-Pad37)") (class "Default")
      (node (ref "J6") (pin "37") (pinfunction "NC37_37") (pintype "passive+no_connect"))
    )
    (net (code "90") (name "unconnected-(J6-NC41-Pad41)") (class "Default")
      (node (ref "J6") (pin "41") (pinfunction "NC41_41") (pintype "passive+no_connect"))
    )
    (net (code "91") (name "unconnected-(J6-NC43-Pad43)") (class "Default")
      (node (ref "J6") (pin "43") (pinfunction "NC43_43") (pintype "passive+no_connect"))
    )
    (net (code "92") (name "unconnected-(J6-NC44-Pad44)") (class "Default")
      (node (ref "J6") (pin "44") (pinfunction "NC44_44") (pintype "passive+no_connect"))
    )
    (net (code "93") (name "unconnected-(J6-NC47-Pad47)") (class "Default")
      (node (ref "J6") (pin "47") (pinfunction "NC47_47") (pintype "passive+no_connect"))
    )
    (net (code "94") (name "unconnected-(J6-NC49-Pad49)") (class "Default")
      (node (ref "J6") (pin "49") (pinfunction "NC49_49") (pintype "passive+no_connect"))
    )
    (net (code "95") (name "unconnected-(J6-NC53-Pad53)") (class "Default")
      (node (ref "J6") (pin "53") (pinfunction "NC53_53") (pintype "passive+no_connect"))
    )
    (net (code "96") (name "unconnected-(J6-NC55-Pad55)") (class "Default")
      (node (ref "J6") (pin "55") (pinfunction "NC55_55") (pintype "passive+no_connect"))
    )
    (net (code "97") (name "unconnected-(J6-NC59-Pad59)") (class "Default")
      (node (ref "J6") (pin "59") (pinfunction "NC59_59") (pintype "passive+no_connect"))
    )
    (net (code "98") (name "unconnected-(J6-NC61-Pad61)") (class "Default")
      (node (ref "J6") (pin "61") (pinfunction "NC61_61") (pintype "passive+no_connect"))
    )
    (net (code "99") (name "unconnected-(J6-NC63-Pad63)") (class "Default")
      (node (ref "J6") (pin "63") (pinfunction "NC63_63") (pintype "passive+no_connect"))
    )
    (net (code "100") (name "unconnected-(J6-NC65-Pad65)") (class "Default")
      (node (ref "J6") (pin "65") (pinfunction "NC65_65") (pintype "passive+no_connect"))
    )
    (net (code "101") (name "unconnected-(J6-NC66-Pad66)") (class "Default")
      (node (ref "J6") (pin "66") (pinfunction "NC66_66") (pintype "passive+no_connect"))
    )
    (net (code "102") (name "unconnected-(J6-NC68-Pad68)") (class "Default")
      (node (ref "J6") (pin "68") (pinfunction "NC68_68") (pintype "passive+no_connect"))
    )
    (net (code "103") (name "unconnected-(J6-NC69-Pad69)") (class "Default")
      (node (ref "J6") (pin "69") (pinfunction "NC69_69") (pintype "passive+no_connect"))
    )
    (net (code "104") (name "unconnected-(J6-NC75-Pad75)") (class "Default")
      (node (ref "J6") (pin "75") (pinfunction "NC75_75") (pintype "passive+no_connect"))
    )
    (net (code "105") (name "unconnected-(J6-VACT_GPS_IN-Pad22)") (class "Default")
      (node (ref "J6") (pin "22") (pinfunction "VACT_GPS_IN_22") (pintype "passive+no_connect"))
    )
    (net (code "106") (name "unconnected-(MOD1-(ARef)-PadJ1.3)") (class "Default")
      (node (ref "MOD1") (pin "J1.3") (pinfunction "(ARef)_J1.3") (pintype "passive"))
    )
    (net (code "107") (name "unconnected-(MOD1-3V-PadJ1.2)") (class "Default")
      (node (ref "MOD1") (pin "J1.2") (pinfunction "3V_J1.2") (pintype "passive"))
    )
    (net (code "108") (name "unconnected-(MOD1-A0-PadJ1.5)") (class "Default")
      (node (ref "MOD1") (pin "J1.5") (pinfunction "A0_J1.5") (pintype "passive"))
    )
    (net (code "109") (name "unconnected-(MOD1-A1-PadJ1.6)") (class "Default")
      (node (ref "MOD1") (pin "J1.6") (pinfunction "A1_J1.6") (pintype "passive"))
    )
    (net (code "110") (name "unconnected-(MOD1-A2-PadJ1.7)") (class "Default")
      (node (ref "MOD1") (pin "J1.7") (pinfunction "A2_J1.7") (pintype "passive"))
    )
    (net (code "111") (name "unconnected-(MOD1-A3-PadJ1.8)") (class "Default")
      (node (ref "MOD1") (pin "J1.8") (pinfunction "A3_J1.8") (pintype "passive"))
    )
    (net (code "112") (name "unconnected-(MOD1-A4-PadJ1.9)") (class "Default")
      (node (ref "MOD1") (pin "J1.9") (pinfunction "A4_J1.9") (pintype "passive"))
    )
    (net (code "113") (name "unconnected-(MOD1-A5-PadJ1.10)") (class "Default")
      (node (ref "MOD1") (pin "J1.10") (pinfunction "A5_J1.10") (pintype "passive"))
    )
    (net (code "114") (name "unconnected-(MOD1-B0-PadJ1.16)") (class "Default")
      (node (ref "MOD1") (pin "J1.16") (pinfunction "B0_J1.16") (pintype "passive"))
    )
    (net (code "115") (name "unconnected-(MOD1-D0(RX)-PadJ1.14)") (class "Default")
      (node (ref "MOD1") (pin "J1.14") (pinfunction "D0(RX)_J1.14") (pintype "passive"))
    )
    (net (code "116") (name "unconnected-(MOD1-D1(TX)-PadJ1.15)") (class "Default")
      (node (ref "MOD1") (pin "J1.15") (pinfunction "D1(TX)_J1.15") (pintype "passive"))
    )
    (net (code "117") (name "unconnected-(MOD1-D5-PadJ3.10)") (class "Default")
      (node (ref "MOD1") (pin "J3.10") (pinfunction "D5_J3.10") (pintype "passive"))
    )
    (net (code "118") (name "unconnected-(MOD1-D6-PadJ3.9)") (class "Default")
      (node (ref "MOD1") (pin "J3.9") (pinfunction "D6_J3.9") (pintype "passive"))
    )
    (net (code "119") (name "unconnected-(MOD1-D9-PadJ3.8)") (class "Default")
      (node (ref "MOD1") (pin "J3.8") (pinfunction "D9_J3.8") (pintype "passive"))
    )
    (net (code "120") (name "unconnected-(MOD1-D10-PadJ3.7)") (class "Default")
      (node (ref "MOD1") (pin "J3.7") (pinfunction "D10_J3.7") (pintype "passive"))
    )
    (net (code "121") (name "unconnected-(MOD1-D11-PadJ3.6)") (class "Default")
      (node (ref "MOD1") (pin "J3.6") (pinfunction "D11_J3.6") (pintype "passive"))
    )
    (net (code "122") (name "unconnected-(MOD1-D12-PadJ3.5)") (class "Default")
      (node (ref "MOD1") (pin "J3.5") (pinfunction "D12_J3.5") (pintype "passive"))
    )
    (net (code "123") (name "unconnected-(MOD1-D13-PadJ3.4)") (class "Default")
      (node (ref "MOD1") (pin "J3.4") (pinfunction "D13_J3.4") (pintype "passive"))
    )
    (net (code "124") (name "unconnected-(MOD1-EN-PadJ3.2)") (class "Default")
      (node (ref "MOD1") (pin "J3.2") (pinfunction "EN_J3.2") (pintype "passive"))
    )
    (net (code "125") (name "unconnected-(MOD1-GND-PadJ1.4)") (class "Default")
      (node (ref "MOD1") (pin "J1.4") (pinfunction "GND_J1.4") (pintype "passive"))
    )
    (net (code "126") (name "unconnected-(MOD1-MISO-PadJ1.13)") (class "Default")
      (node (ref "MOD1") (pin "J1.13") (pinfunction "MISO_J1.13") (pintype "passive"))
    )
    (net (code "127") (name "unconnected-(MOD1-MOSI-PadJ1.12)") (class "Default")
      (node (ref "MOD1") (pin "J1.12") (pinfunction "MOSI_J1.12") (pintype "passive"))
    )
    (net (code "128") (name "unconnected-(MOD1-RESET#-PadJ1.1)") (class "Default")
      (node (ref "MOD1") (pin "J1.1") (pinfunction "RESET#_J1.1") (pintype "passive"))
    )
    (net (code "129") (name "unconnected-(MOD1-SCK-PadJ1.11)") (class "Default")
      (node (ref "MOD1") (pin "J1.11") (pinfunction "SCK_J1.11") (pintype "passive"))
    )
    (net (code "130") (name "unconnected-(MOD1-SCL-PadJ3.11)") (class "Default")
      (node (ref "MOD1") (pin "J3.11") (pinfunction "SCL_J3.11") (pintype "passive"))
    )
    (net (code "131") (name "unconnected-(MOD1-SDA-PadJ3.12)") (class "Default")
      (node (ref "MOD1") (pin "J3.12") (pinfunction "SDA_J3.12") (pintype "passive"))
    )
    (net (code "132") (name "unconnected-(MOD1-VBAT-PadJ3.1)") (class "Default")
      (node (ref "MOD1") (pin "J3.1") (pinfunction "VBAT_J3.1") (pintype "passive"))
    )
    (net (code "133") (name "unconnected-(MOD1-VBUS-PadJ3.3)") (class "Default")
      (node (ref "MOD1") (pin "J3.3") (pinfunction "VBUS_J3.3") (pintype "passive"))
    )
    (net (code "134") (name "unconnected-(MOD1L-Pad2)") (class "Default")
      (node (ref "MOD1L") (pin "2") (pinfunction "2_2") (pintype "passive+no_connect"))
    )
    (net (code "135") (name "unconnected-(RR1-Pad7)") (class "Default")
      (node (ref "RR1") (pin "7") (pinfunction "7_7") (pintype "passive+no_connect"))
    )
    (net (code "136") (name "unconnected-(RR1-Pad8)") (class "Default")
      (node (ref "RR1") (pin "8") (pinfunction "8_8") (pintype "passive+no_connect"))
    )
    (net (code "137") (name "unconnected-(RR2-Pad9)") (class "Default")
      (node (ref "RR2") (pin "9") (pinfunction "9_9") (pintype "passive+no_connect"))
    )
    (net (code "138") (name "unconnected-(RR2-Pad10)") (class "Default")
      (node (ref "RR2") (pin "10") (pinfunction "10_10") (pintype "passive+no_connect"))
    )
  )
)
